# SubBus7.net
KiCad netlist of a schematic drawn in Altium Designer
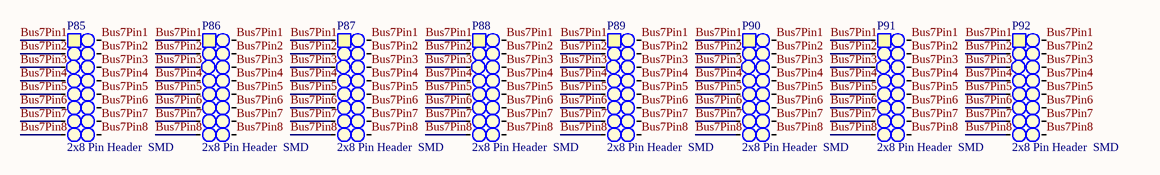
[diagram p0: SubBus7.SchDoc]

(export (version "E")
  (design (tool "Eeschema 10.0.6"))
  (components
    (comp (ref "P85")
      (value "2x8 Pin Header  SMD")
      (footprint "2X8_SMD_PH_2.54")
      (description "2.54mm, SMD")
      (libsource (lib "jclib") (part "2x8 Pin Header  SMD"))
    )
    (comp (ref "P86")
      (value "2x8 Pin Header  SMD")
      (footprint "2X8_SMD_PH_2.54")
      (description "2.54mm, SMD")
      (libsource (lib "jclib") (part "2x8 Pin Header  SMD"))
    )
    (comp (ref "P87")
      (value "2x8 Pin Header  SMD")
      (footprint "2X8_SMD_PH_2.54")
      (description "2.54mm, SMD")
      (libsource (lib "jclib") (part "2x8 Pin Header  SMD"))
    )
    (comp (ref "P88")
      (value "2x8 Pin Header  SMD")
      (footprint "2X8_SMD_PH_2.54")
      (description "2.54mm, SMD")
      (libsource (lib "jclib") (part "2x8 Pin Header  SMD"))
    )
    (comp (ref "P89")
      (value "2x8 Pin Header  SMD")
      (footprint "2X8_SMD_PH_2.54")
      (description "2.54mm, SMD")
      (libsource (lib "jclib") (part "2x8 Pin Header  SMD"))
    )
    (comp (ref "P90")
      (value "2x8 Pin Header  SMD")
      (footprint "2X8_SMD_PH_2.54")
      (description "2.54mm, SMD")
      (libsource (lib "jclib") (part "2x8 Pin Header  SMD"))
    )
    (comp (ref "P91")
      (value "2x8 Pin Header  SMD")
      (footprint "2X8_SMD_PH_2.54")
      (description "2.54mm, SMD")
      (libsource (lib "jclib") (part "2x8 Pin Header  SMD"))
    )
    (comp (ref "P92")
      (value "2x8 Pin Header  SMD")
      (footprint "2X8_SMD_PH_2.54")
      (description "2.54mm, SMD")
      (libsource (lib "jclib") (part "2x8 Pin Header  SMD"))
    )
  )
  (nets
    (net (code "1") (name "/Bus7Pin1") (class "Default")
      (node (ref "P85") (pin "1") (pinfunction "1_1") (pintype "passive"))
      (node (ref "P85") (pin "16") (pinfunction "16_16") (pintype "passive"))
      (node (ref "P86") (pin "1") (pinfunction "1_1") (pintype "passive"))
      (node (ref "P86") (pin "16") (pinfunction "16_16") (pintype "passive"))
      (node (ref "P87") (pin "1") (pinfunction "1_1") (pintype "passive"))
      (node (ref "P87") (pin "16") (pinfunction "16_16") (pintype "passive"))
      (node (ref "P88") (pin "1") (pinfunction "1_1") (pintype "passive"))
      (node (ref "P88") (pin "16") (pinfunction "16_16") (pintype "passive"))
      (node (ref "P89") (pin "1") (pinfunction "1_1") (pintype "passive"))
      (node (ref "P89") (pin "16") (pinfunction "16_16") (pintype "passive"))
      (node (ref "P90") (pin "1") (pinfunction "1_1") (pintype "passive"))
      (node (ref "P90") (pin "16") (pinfunction "16_16") (pintype "passive"))
      (node (ref "P91") (pin "1") (pinfunction "1_1") (pintype "passive"))
      (node (ref "P91") (pin "16") (pinfunction "16_16") (pintype "passive"))
      (node (ref "P92") (pin "1") (pinfunction "1_1") (pintype "passive"))
      (node (ref "P92") (pin "16") (pinfunction "16_16") (pintype "passive"))
    )
    (net (code "2") (name "/Bus7Pin2") (class "Default")
      (node (ref "P85") (pin "15") (pinfunction "15_15") (pintype "passive"))
      (node (ref "P85") (pin "2") (pinfunction "2_2") (pintype "passive"))
      (node (ref "P86") (pin "15") (pinfunction "15_15") (pintype "passive"))
      (node (ref "P86") (pin "2") (pinfunction "2_2") (pintype "passive"))
      (node (ref "P87") (pin "15") (pinfunction "15_15") (pintype "passive"))
      (node (ref "P87") (pin "2") (pinfunction "2_2") (pintype "passive"))
      (node (ref "P88") (pin "15") (pinfunction "15_15") (pintype "passive"))
      (node (ref "P88") (pin "2") (pinfunction "2_2") (pintype "passive"))
      (node (ref "P89") (pin "15") (pinfunction "15_15") (pintype "passive"))
      (node (ref "P89") (pin "2") (pinfunction "2_2") (pintype "passive"))
      (node (ref "P90") (pin "15") (pinfunction "15_15") (pintype "passive"))
      (node (ref "P90") (pin "2") (pinfunction "2_2") (pintype "passive"))
      (node (ref "P91") (pin "15") (pinfunction "15_15") (pintype "passive"))
      (node (ref "P91") (pin "2") (pinfunction "2_2") (pintype "passive"))
      (node (ref "P92") (pin "15") (pinfunction "15_15") (pintype "passive"))
      (node (ref "P92") (pin "2") (pinfunction "2_2") (pintype "passive"))
    )
    (net (code "3") (name "/Bus7Pin3") (class "Default")
      (node (ref "P85") (pin "14") (pinfunction "14_14") (pintype "passive"))
      (node (ref "P85") (pin "3") (pinfunction "3_3") (pintype "passive"))
      (node (ref "P86") (pin "14") (pinfunction "14_14") (pintype "passive"))
      (node (ref "P86") (pin "3") (pinfunction "3_3") (pintype "passive"))
      (node (ref "P87") (pin "14") (pinfunction "14_14") (pintype "passive"))
      (node (ref "P87") (pin "3") (pinfunction "3_3") (pintype "passive"))
      (node (ref "P88") (pin "14") (pinfunction "14_14") (pintype "passive"))
      (node (ref "P88") (pin "3") (pinfunction "3_3") (pintype "passive"))
      (node (ref "P89") (pin "14") (pinfunction "14_14") (pintype "passive"))
      (node (ref "P89") (pin "3") (pinfunction "3_3") (pintype "passive"))
      (node (ref "P90") (pin "14") (pinfunction "14_14") (pintype "passive"))
      (node (ref "P90") (pin "3") (pinfunction "3_3") (pintype "passive"))
      (node (ref "P91") (pin "14") (pinfunction "14_14") (pintype "passive"))
      (node (ref "P91") (pin "3") (pinfunction "3_3") (pintype "passive"))
      (node (ref "P92") (pin "14") (pinfunction "14_14") (pintype "passive"))
      (node (ref "P92") (pin "3") (pinfunction "3_3") (pintype "passive"))
    )
    (net (code "4") (name "/Bus7Pin4") (class "Default")
      (node (ref "P85") (pin "13") (pinfunction "13_13") (pintype "passive"))
      (node (ref "P85") (pin "4") (pinfunction "4_4") (pintype "passive"))
      (node (ref "P86") (pin "13") (pinfunction "13_13") (pintype "passive"))
      (node (ref "P86") (pin "4") (pinfunction "4_4") (pintype "passive"))
      (node (ref "P87") (pin "13") (pinfunction "13_13") (pintype "passive"))
      (node (ref "P87") (pin "4") (pinfunction "4_4") (pintype "passive"))
      (node (ref "P88") (pin "13") (pinfunction "13_13") (pintype "passive"))
      (node (ref "P88") (pin "4") (pinfunction "4_4") (pintype "passive"))
      (node (ref "P89") (pin "13") (pinfunction "13_13") (pintype "passive"))
      (node (ref "P89") (pin "4") (pinfunction "4_4") (pintype "passive"))
      (node (ref "P90") (pin "13") (pinfunction "13_13") (pintype "passive"))
      (node (ref "P90") (pin "4") (pinfunction "4_4") (pintype "passive"))
      (node (ref "P91") (pin "13") (pinfunction "13_13") (pintype "passive"))
      (node (ref "P91") (pin "4") (pinfunction "4_4") (pintype "passive"))
      (node (ref "P92") (pin "13") (pinfunction "13_13") (pintype "passive"))
      (node (ref "P92") (pin "4") (pinfunction "4_4") (pintype "passive"))
    )
    (net (code "5") (name "/Bus7Pin5") (class "Default")
      (node (ref "P85") (pin "12") (pinfunction "12_12") (pintype "passive"))
      (node (ref "P85") (pin "5") (pinfunction "5_5") (pintype "passive"))
      (node (ref "P86") (pin "12") (pinfunction "12_12") (pintype "passive"))
      (node (ref "P86") (pin "5") (pinfunction "5_5") (pintype "passive"))
      (node (ref "P87") (pin "12") (pinfunction "12_12") (pintype "passive"))
      (node (ref "P87") (pin "5") (pinfunction "5_5") (pintype "passive"))
      (node (ref "P88") (pin "12") (pinfunction "12_12") (pintype "passive"))
      (node (ref "P88") (pin "5") (pinfunction "5_5") (pintype "passive"))
      (node (ref "P89") (pin "12") (pinfunction "12_12") (pintype "passive"))
      (node (ref "P89") (pin "5") (pinfunction "5_5") (pintype "passive"))
      (node (ref "P90") (pin "12") (pinfunction "12_12") (pintype "passive"))
      (node (ref "P90") (pin "5") (pinfunction "5_5") (pintype "passive"))
      (node (ref "P91") (pin "12") (pinfunction "12_12") (pintype "passive"))
      (node (ref "P91") (pin "5") (pinfunction "5_5") (pintype "passive"))
      (node (ref "P92") (pin "12") (pinfunction "12_12") (pintype "passive"))
      (node (ref "P92") (pin "5") (pinfunction "5_5") (pintype "passive"))
    )
    (net (code "6") (name "/Bus7Pin6") (class "Default")
      (node (ref "P85") (pin "11") (pinfunction "11_11") (pintype "passive"))
      (node (ref "P85") (pin "6") (pinfunction "6_6") (pintype "passive"))
      (node (ref "P86") (pin "11") (pinfunction "11_11") (pintype "passive"))
      (node (ref "P86") (pin "6") (pinfunction "6_6") (pintype "passive"))
      (node (ref "P87") (pin "11") (pinfunction "11_11") (pintype "passive"))
      (node (ref "P87") (pin "6") (pinfunction "6_6") (pintype "passive"))
      (node (ref "P88") (pin "11") (pinfunction "11_11") (pintype "passive"))
      (node (ref "P88") (pin "6") (pinfunction "6_6") (pintype "passive"))
      (node (ref "P89") (pin "11") (pinfunction "11_11") (pintype "passive"))
      (node (ref "P89") (pin "6") (pinfunction "6_6") (pintype "passive"))
      (node (ref "P90") (pin "11") (pinfunction "11_11") (pintype "passive"))
      (node (ref "P90") (pin "6") (pinfunction "6_6") (pintype "passive"))
      (node (ref "P91") (pin "11") (pinfunction "11_11") (pintype "passive"))
      (node (ref "P91") (pin "6") (pinfunction "6_6") (pintype "passive"))
      (node (ref "P92") (pin "11") (pinfunction "11_11") (pintype "passive"))
      (node (ref "P92") (pin "6") (pinfunction "6_6") (pintype "passive"))
    )
    (net (code "7") (name "/Bus7Pin7") (class "Default")
      (node (ref "P85") (pin "10") (pinfunction "10_10") (pintype "passive"))
      (node (ref "P85") (pin "7") (pinfunction "7_7") (pintype "passive"))
      (node (ref "P86") (pin "10") (pinfunction "10_10") (pintype "passive"))
      (node (ref "P86") (pin "7") (pinfunction "7_7") (pintype "passive"))
      (node (ref "P87") (pin "10") (pinfunction "10_10") (pintype "passive"))
      (node (ref "P87") (pin "7") (pinfunction "7_7") (pintype "passive"))
      (node (ref "P88") (pin "10") (pinfunction "10_10") (pintype "passive"))
      (node (ref "P88") (pin "7") (pinfunction "7_7") (pintype "passive"))
      (node (ref "P89") (pin "10") (pinfunction "10_10") (pintype "passive"))
      (node (ref "P89") (pin "7") (pinfunction "7_7") (pintype "passive"))
      (node (ref "P90") (pin "10") (pinfunction "10_10") (pintype "passive"))
      (node (ref "P90") (pin "7") (pinfunction "7_7") (pintype "passive"))
      (node (ref "P91") (pin "10") (pinfunction "10_10") (pintype "passive"))
      (node (ref "P91") (pin "7") (pinfunction "7_7") (pintype "passive"))
      (node (ref "P92") (pin "10") (pinfunction "10_10") (pintype "passive"))
      (node (ref "P92") (pin "7") (pinfunction "7_7") (pintype "passive"))
    )
    (net (code "8") (name "/Bus7Pin8") (class "Default")
      (node (ref "P85") (pin "8") (pinfunction "8_8") (pintype "passive"))
      (node (ref "P85") (pin "9") (pinfunction "9_9") (pintype "passive"))
      (node (ref "P86") (pin "8") (pinfunction "8_8") (pintype "passive"))
      (node (ref "P86") (pin "9") (pinfunction "9_9") (pintype "passive"))
      (node (ref "P87") (pin "8") (pinfunction "8_8") (pintype "passive"))
      (node (ref "P87") (pin "9") (pinfunction "9_9") (pintype "passive"))
      (node (ref "P88") (pin "8") (pinfunction "8_8") (pintype "passive"))
      (node (ref "P88") (pin "9") (pinfunction "9_9") (pintype "passive"))
      (node (ref "P89") (pin "8") (pinfunction "8_8") (pintype "passive"))
      (node (ref "P89") (pin "9") (pinfunction "9_9") (pintype "passive"))
      (node (ref "P90") (pin "8") (pinfunction "8_8") (pintype "passive"))
      (node (ref "P90") (pin "9") (pinfunction "9_9") (pintype "passive"))
      (node (ref "P91") (pin "8") (pinfunction "8_8") (pintype "passive"))
      (node (ref "P91") (pin "9") (pinfunction "9_9") (pintype "passive"))
      (node (ref "P92") (pin "8") (pinfunction "8_8") (pintype "passive"))
      (node (ref "P92") (pin "9") (pinfunction "9_9") (pintype "passive"))
    )
  )
)
